# version10_25.net
KiCad netlist of a schematic drawn in EAGLE
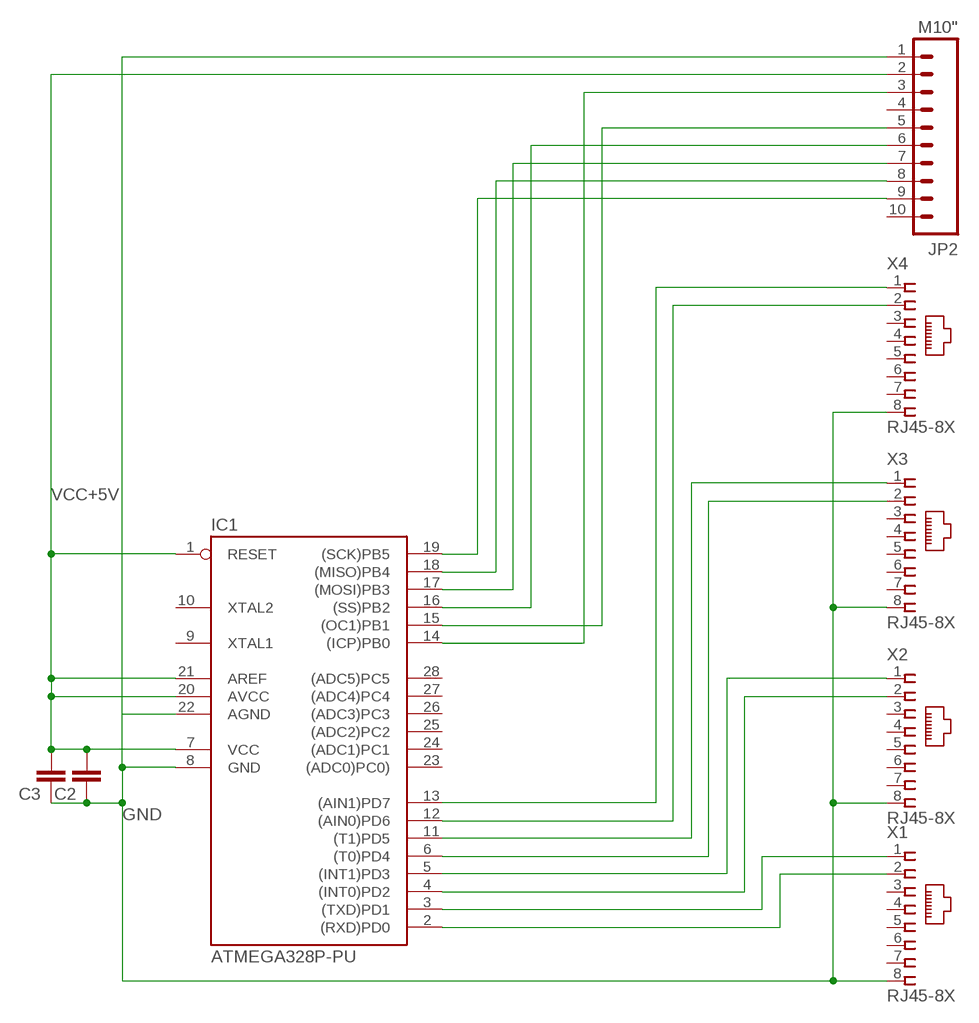
[diagram p0: schematic, sheet 1]

(export (version "E")
  (design (tool "Eeschema 10.0.6"))
  (components
    (comp (ref "C2")
      (value "CAP1206")
      (footprint "eagle-import:1206")
      (libsource (lib "eagle-import") (part "CAP1206"))
    )
    (comp (ref "C3")
      (value "CAP1206")
      (footprint "eagle-import:1206")
      (libsource (lib "eagle-import") (part "CAP1206"))
    )
    (comp (ref "IC1")
      (value "ATMEGA328P-PU")
      (footprint "eagle-import:DIL28-3")
      (libsource (lib "eagle-import") (part "ATMEGA328P-PU"))
    )
    (comp (ref "JP2")
      (value "M10\"")
      (footprint "eagle-import:1X10")
      (libsource (lib "eagle-import") (part "M10{dblquote}"))
    )
    (comp (ref "X1")
      (value "RJ45-8X")
      (footprint "eagle-import:RJ45-NO-SHIELD")
      (libsource (lib "eagle-import") (part "RJ45-8X"))
    )
    (comp (ref "X2")
      (value "RJ45-8X")
      (footprint "eagle-import:RJ45-NO-SHIELD")
      (libsource (lib "eagle-import") (part "RJ45-8X"))
    )
    (comp (ref "X3")
      (value "RJ45-8X")
      (footprint "eagle-import:RJ45-NO-SHIELD")
      (libsource (lib "eagle-import") (part "RJ45-8X"))
    )
    (comp (ref "X4")
      (value "RJ45-8X")
      (footprint "eagle-import:RJ45-NO-SHIELD")
      (libsource (lib "eagle-import") (part "RJ45-8X"))
    )
  )
  (nets
    (net (code "1") (name "/GND") (class "Default")
      (node (ref "C2") (pin "1") (pinfunction "1_1") (pintype "passive"))
      (node (ref "C3") (pin "1") (pinfunction "1_1") (pintype "passive"))
      (node (ref "IC1") (pin "22") (pinfunction "AGND_22") (pintype "power_in"))
      (node (ref "IC1") (pin "8") (pinfunction "GND_8") (pintype "power_in"))
      (node (ref "JP2") (pin "1") (pinfunction "1_1") (pintype "passive"))
      (node (ref "X1") (pin "8") (pinfunction "8_8") (pintype "passive"))
      (node (ref "X2") (pin "8") (pinfunction "8_8") (pintype "passive"))
      (node (ref "X3") (pin "8") (pinfunction "8_8") (pintype "passive"))
      (node (ref "X4") (pin "8") (pinfunction "8_8") (pintype "passive"))
    )
    (net (code "2") (name "/VCC+5V") (class "Default")
      (node (ref "C2") (pin "2") (pinfunction "2_2") (pintype "passive"))
      (node (ref "C3") (pin "2") (pinfunction "2_2") (pintype "passive"))
      (node (ref "IC1") (pin "1") (pinfunction "RESET_1") (pintype "input"))
      (node (ref "IC1") (pin "20") (pinfunction "AVCC_20") (pintype "power_in"))
      (node (ref "IC1") (pin "21") (pinfunction "AREF_21") (pintype "passive"))
      (node (ref "IC1") (pin "7") (pinfunction "VCC_7") (pintype "power_in"))
      (node (ref "JP2") (pin "2") (pinfunction "2_2") (pintype "passive"))
    )
    (net (code "3") (name "Net-(IC1-(AIN0)PD6)") (class "Default")
      (node (ref "IC1") (pin "12") (pinfunction "(AIN0)PD6_12") (pintype "bidirectional"))
      (node (ref "X4") (pin "2") (pinfunction "2_2") (pintype "passive"))
    )
    (net (code "4") (name "Net-(IC1-(AIN1)PD7)") (class "Default")
      (node (ref "IC1") (pin "13") (pinfunction "(AIN1)PD7_13") (pintype "bidirectional"))
      (node (ref "X4") (pin "1") (pinfunction "1_1") (pintype "passive"))
    )
    (net (code "5") (name "Net-(IC1-(ICP)PB0)") (class "Default")
      (node (ref "IC1") (pin "14") (pinfunction "(ICP)PB0_14") (pintype "bidirectional"))
      (node (ref "JP2") (pin "3") (pinfunction "3_3") (pintype "passive"))
    )
    (net (code "6") (name "Net-(IC1-(INT0)PD2)") (class "Default")
      (node (ref "IC1") (pin "4") (pinfunction "(INT0)PD2_4") (pintype "bidirectional"))
      (node (ref "X2") (pin "2") (pinfunction "2_2") (pintype "passive"))
    )
    (net (code "7") (name "Net-(IC1-(INT1)PD3)") (class "Default")
      (node (ref "IC1") (pin "5") (pinfunction "(INT1)PD3_5") (pintype "bidirectional"))
      (node (ref "X2") (pin "1") (pinfunction "1_1") (pintype "passive"))
    )
    (net (code "8") (name "Net-(IC1-(MISO)PB4)") (class "Default")
      (node (ref "IC1") (pin "18") (pinfunction "(MISO)PB4_18") (pintype "bidirectional"))
      (node (ref "JP2") (pin "8") (pinfunction "8_8") (pintype "passive"))
    )
    (net (code "9") (name "Net-(IC1-(MOSI)PB3)") (class "Default")
      (node (ref "IC1") (pin "17") (pinfunction "(MOSI)PB3_17") (pintype "bidirectional"))
      (node (ref "JP2") (pin "7") (pinfunction "7_7") (pintype "passive"))
    )
    (net (code "10") (name "Net-(IC1-(OC1)PB1)") (class "Default")
      (node (ref "IC1") (pin "15") (pinfunction "(OC1)PB1_15") (pintype "bidirectional"))
      (node (ref "JP2") (pin "5") (pinfunction "5_5") (pintype "passive"))
    )
    (net (code "11") (name "Net-(IC1-(RXD)PD0)") (class "Default")
      (node (ref "IC1") (pin "2") (pinfunction "(RXD)PD0_2") (pintype "bidirectional"))
      (node (ref "X1") (pin "2") (pinfunction "2_2") (pintype "passive"))
    )
    (net (code "12") (name "Net-(IC1-(SCK)PB5)") (class "Default")
      (node (ref "IC1") (pin "19") (pinfunction "(SCK)PB5_19") (pintype "bidirectional"))
      (node (ref "JP2") (pin "9") (pinfunction "9_9") (pintype "passive"))
    )
    (net (code "13") (name "Net-(IC1-(SS)PB2)") (class "Default")
      (node (ref "IC1") (pin "16") (pinfunction "(SS)PB2_16") (pintype "bidirectional"))
      (node (ref "JP2") (pin "6") (pinfunction "6_6") (pintype "passive"))
    )
    (net (code "14") (name "Net-(IC1-(T0)PD4)") (class "Default")
      (node (ref "IC1") (pin "6") (pinfunction "(T0)PD4_6") (pintype "bidirectional"))
      (node (ref "X3") (pin "2") (pinfunction "2_2") (pintype "passive"))
    )
    (net (code "15") (name "Net-(IC1-(T1)PD5)") (class "Default")
      (node (ref "IC1") (pin "11") (pinfunction "(T1)PD5_11") (pintype "bidirectional"))
      (node (ref "X3") (pin "1") (pinfunction "1_1") (pintype "passive"))
    )
    (net (code "16") (name "Net-(IC1-(TXD)PD1)") (class "Default")
      (node (ref "IC1") (pin "3") (pinfunction "(TXD)PD1_3") (pintype "bidirectional"))
      (node (ref "X1") (pin "1") (pinfunction "1_1") (pintype "passive"))
    )
    (net (code "17") (name "unconnected-(IC1-(ADC0)PC0)-Pad23)") (class "Default")
      (node (ref "IC1") (pin "23") (pinfunction "(ADC0)PC0)_23") (pintype "bidirectional"))
    )
    (net (code "18") (name "unconnected-(IC1-(ADC1)PC1-Pad24)") (class "Default")
      (node (ref "IC1") (pin "24") (pinfunction "(ADC1)PC1_24") (pintype "bidirectional"))
    )
    (net (code "19") (name "unconnected-(IC1-(ADC2)PC2-Pad25)") (class "Default")
      (node (ref "IC1") (pin "25") (pinfunction "(ADC2)PC2_25") (pintype "bidirectional"))
    )
    (net (code "20") (name "unconnected-(IC1-(ADC3)PC3-Pad26)") (class "Default")
      (node (ref "IC1") (pin "26") (pinfunction "(ADC3)PC3_26") (pintype "bidirectional"))
    )
    (net (code "21") (name "unconnected-(IC1-(ADC4)PC4-Pad27)") (class "Default")
      (node (ref "IC1") (pin "27") (pinfunction "(ADC4)PC4_27") (pintype "bidirectional"))
    )
    (net (code "22") (name "unconnected-(IC1-(ADC5)PC5-Pad28)") (class "Default")
      (node (ref "IC1") (pin "28") (pinfunction "(ADC5)PC5_28") (pintype "bidirectional"))
    )
    (net (code "23") (name "unconnected-(IC1-XTAL1-Pad9)") (class "Default")
      (node (ref "IC1") (pin "9") (pinfunction "XTAL1_9") (pintype "bidirectional"))
    )
    (net (code "24") (name "unconnected-(IC1-XTAL2-Pad10)") (class "Default")
      (node (ref "IC1") (pin "10") (pinfunction "XTAL2_10") (pintype "bidirectional"))
    )
    (net (code "25") (name "unconnected-(JP2-Pad4)") (class "Default")
      (node (ref "JP2") (pin "4") (pinfunction "4_4") (pintype "passive"))
    )
    (net (code "26") (name "unconnected-(JP2-Pad10)") (class "Default")
      (node (ref "JP2") (pin "10") (pinfunction "10_10") (pintype "passive"))
    )
    (net (code "27") (name "unconnected-(X1-Pad3)") (class "Default")
      (node (ref "X1") (pin "3") (pinfunction "3_3") (pintype "passive"))
    )
    (net (code "28") (name "unconnected-(X1-Pad4)") (class "Default")
      (node (ref "X1") (pin "4") (pinfunction "4_4") (pintype "passive"))
    )
    (net (code "29") (name "unconnected-(X1-Pad5)") (class "Default")
      (node (ref "X1") (pin "5") (pinfunction "5_5") (pintype "passive"))
    )
    (net (code "30") (name "unconnected-(X1-Pad6)") (class "Default")
      (node (ref "X1") (pin "6") (pinfunction "6_6") (pintype "passive"))
    )
    (net (code "31") (name "unconnected-(X1-Pad7)") (class "Default")
      (node (ref "X1") (pin "7") (pinfunction "7_7") (pintype "passive"))
    )
    (net (code "32") (name "unconnected-(X2-Pad3)") (class "Default")
      (node (ref "X2") (pin "3") (pinfunction "3_3") (pintype "passive"))
    )
    (net (code "33") (name "unconnected-(X2-Pad4)") (class "Default")
      (node (ref "X2") (pin "4") (pinfunction "4_4") (pintype "passive"))
    )
    (net (code "34") (name "unconnected-(X2-Pad5)") (class "Default")
      (node (ref "X2") (pin "5") (pinfunction "5_5") (pintype "passive"))
    )
    (net (code "35") (name "unconnected-(X2-Pad6)") (class "Default")
      (node (ref "X2") (pin "6") (pinfunction "6_6") (pintype "passive"))
    )
    (net (code "36") (name "unconnected-(X2-Pad7)") (class "Default")
      (node (ref "X2") (pin "7") (pinfunction "7_7") (pintype "passive"))
    )
    (net (code "37") (name "unconnected-(X3-Pad3)") (class "Default")
      (node (ref "X3") (pin "3") (pinfunction "3_3") (pintype "passive"))
    )
    (net (code "38") (name "unconnected-(X3-Pad4)") (class "Default")
      (node (ref "X3") (pin "4") (pinfunction "4_4") (pintype "passive"))
    )
    (net (code "39") (name "unconnected-(X3-Pad5)") (class "Default")
      (node (ref "X3") (pin "5") (pinfunction "5_5") (pintype "passive"))
    )
    (net (code "40") (name "unconnected-(X3-Pad6)") (class "Default")
      (node (ref "X3") (pin "6") (pinfunction "6_6") (pintype "passive"))
    )
    (net (code "41") (name "unconnected-(X3-Pad7)") (class "Default")
      (node (ref "X3") (pin "7") (pinfunction "7_7") (pintype "passive"))
    )
    (net (code "42") (name "unconnected-(X4-Pad3)") (class "Default")
      (node (ref "X4") (pin "3") (pinfunction "3_3") (pintype "passive"))
    )
    (net (code "43") (name "unconnected-(X4-Pad4)") (class "Default")
      (node (ref "X4") (pin "4") (pinfunction "4_4") (pintype "passive"))
    )
    (net (code "44") (name "unconnected-(X4-Pad5)") (class "Default")
      (node (ref "X4") (pin "5") (pinfunction "5_5") (pintype "passive"))
    )
    (net (code "45") (name "unconnected-(X4-Pad6)") (class "Default")
      (node (ref "X4") (pin "6") (pinfunction "6_6") (pintype "passive"))
    )
    (net (code "46") (name "unconnected-(X4-Pad7)") (class "Default")
      (node (ref "X4") (pin "7") (pinfunction "7_7") (pintype "passive"))
    )
  )
)
